# WirelessJoystick.net
KiCad netlist of a schematic drawn in Altium Designer
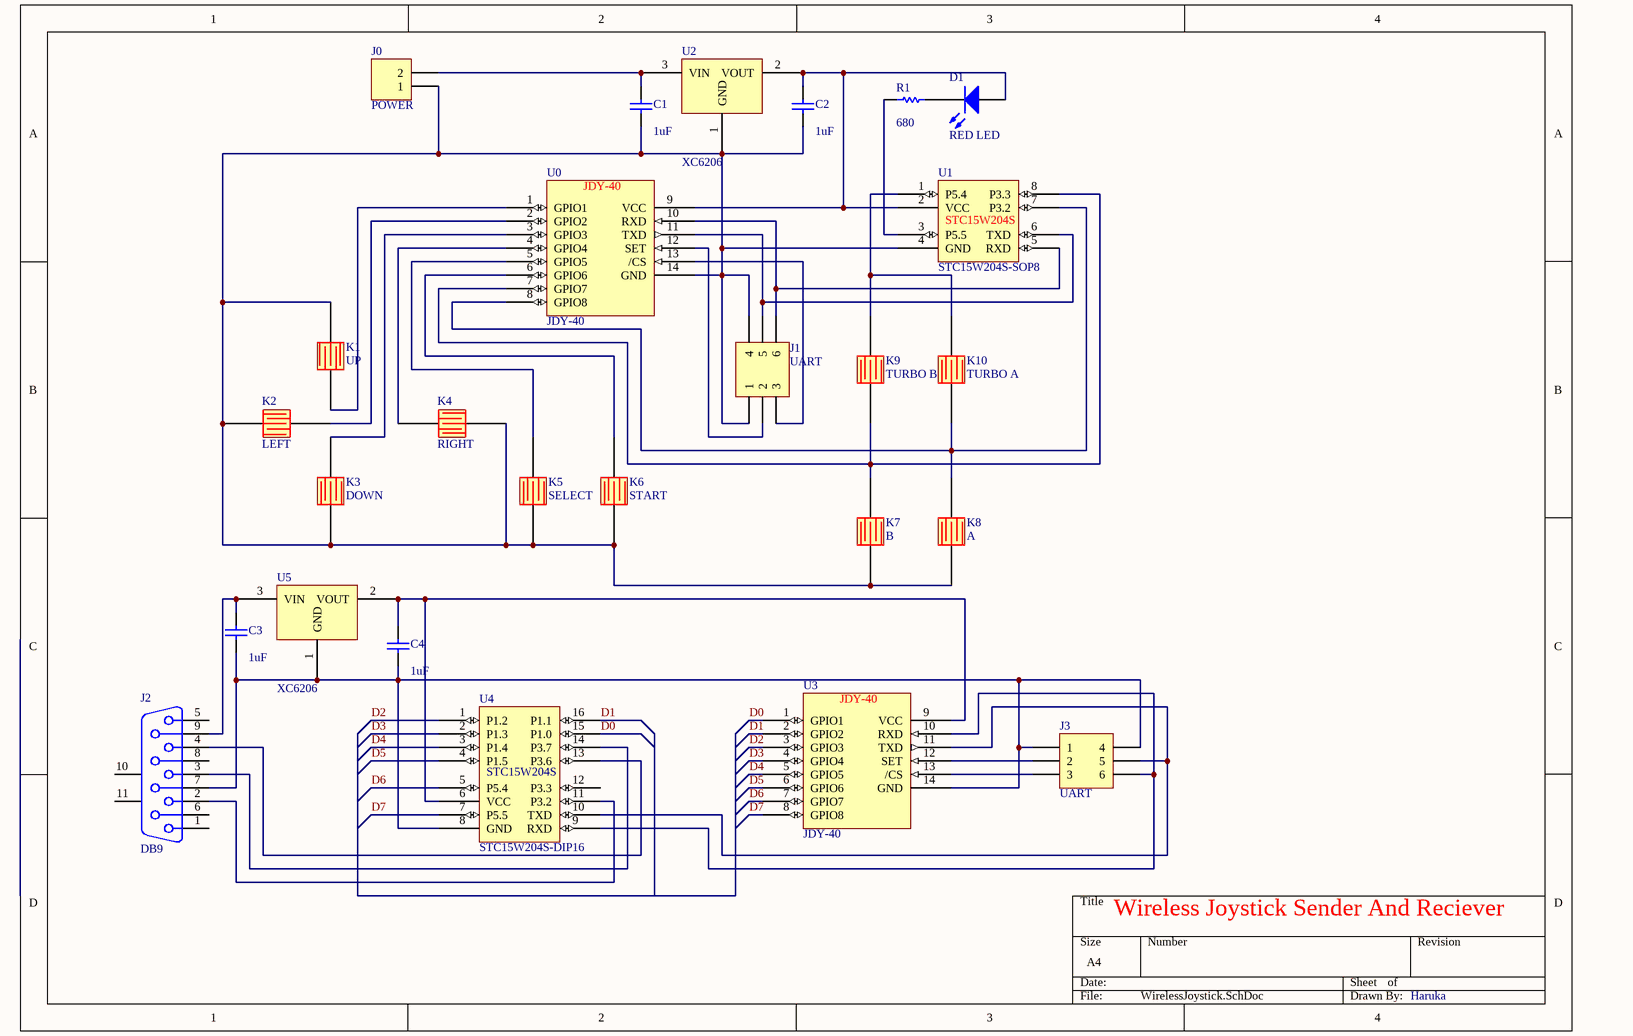
[diagram p0: WirelessJoystick.SchDoc]

(export (version "E")
  (design (tool "Eeschema 10.0.6"))
  (components
    (comp (ref "C1")
      (value "1uF")
      (footprint "C1206")
      (description "Capacitor (Semiconductor SIM Model)")
      (fields (field (name "Comment") "Cap Semi") (field (name "PUBLISHER") "Altium Limited"))
      (libsource (lib "Miscellaneous Devices") (part "Cap Semi"))
    )
    (comp (ref "C2")
      (value "1uF")
      (footprint "C1206")
      (description "Capacitor (Semiconductor SIM Model)")
      (fields (field (name "Comment") "Cap Semi") (field (name "PUBLISHER") "Altium Limited"))
      (libsource (lib "Miscellaneous Devices") (part "Cap Semi"))
    )
    (comp (ref "C3")
      (value "1uF")
      (footprint "C1206")
      (description "Capacitor (Semiconductor SIM Model)")
      (fields (field (name "Comment") "Cap Semi") (field (name "PUBLISHER") "Altium Limited"))
      (libsource (lib "Miscellaneous Devices") (part "Cap Semi"))
    )
    (comp (ref "C4")
      (value "1uF")
      (footprint "C1206")
      (description "Capacitor (Semiconductor SIM Model)")
      (fields (field (name "Comment") "Cap Semi") (field (name "PUBLISHER") "Altium Limited"))
      (libsource (lib "Miscellaneous Devices") (part "Cap Semi"))
    )
    (comp (ref "D1")
      (value "RED LED")
      (footprint "LED-0")
      (description "Typical INFRARED GaAs LED")
      (fields (field (name "PUBLISHER") "Altium Limited"))
      (libsource (lib "Miscellaneous Devices") (part "LED0"))
    )
    (comp (ref "J0")
      (value "POWER")
      (footprint "HDR1X2")
      (description "Header, 2-Pin")
      (fields (field (name "PUBLISHER") "Altium Limited"))
      (libsource (lib "Miscellaneous Connectors") (part "Header 2"))
    )
    (comp (ref "J1")
      (value "UART")
      (footprint "HDR2X3_CEN")
      (description "Header, 3-Pin, Dual row")
      (fields (field (name "PUBLISHER") "Altium Limited"))
      (libsource (lib "") (part "Header 3X2A_1"))
    )
    (comp (ref "J2")
      (value "DB9")
      (footprint "DSUB1.385-2H9")
      (description "Receptacle Assembly, 9 Position, Right Angle")
      (fields (field (name "PUBLISHER") "Altium Limited"))
      (libsource (lib "Miscellaneous Connectors") (part "D Connector 9"))
    )
    (comp (ref "J3")
      (value "UART")
      (footprint "HDR2X3_CEN")
      (description "Header, 3-Pin, Dual row")
      (fields (field (name "PUBLISHER") "Altium Limited"))
      (libsource (lib "Miscellaneous Connectors") (part "Header 3X2A"))
    )
    (comp (ref "K1") (value "UP") (footprint "GoldFinger") (libsource (lib "") (part "GoldFinger_3")))
    (comp (ref "K2") (value "LEFT") (footprint "GoldFinger") (libsource (lib "") (part "GoldFinger_1")))
    (comp (ref "K3")
      (value "DOWN")
      (footprint "GoldFinger")
      (libsource (lib "GoldFinger") (part "GoldFinger"))
    )
    (comp (ref "K4") (value "RIGHT") (footprint "GoldFinger") (libsource (lib "") (part "GoldFinger_2")))
    (comp (ref "K5")
      (value "SELECT")
      (footprint "GoldFinger")
      (libsource (lib "GoldFinger") (part "GoldFinger"))
    )
    (comp (ref "K6")
      (value "START")
      (footprint "GoldFinger")
      (libsource (lib "GoldFinger") (part "GoldFinger"))
    )
    (comp (ref "K7") (value "B") (footprint "GoldFinger") (libsource (lib "GoldFinger") (part "GoldFinger")))
    (comp (ref "K8") (value "A") (footprint "GoldFinger") (libsource (lib "GoldFinger") (part "GoldFinger")))
    (comp (ref "K9")
      (value "TURBO B")
      (footprint "GoldFinger")
      (libsource (lib "GoldFinger") (part "GoldFinger"))
    )
    (comp (ref "K10")
      (value "TURBO A")
      (footprint "GoldFinger")
      (libsource (lib "GoldFinger") (part "GoldFinger"))
    )
    (comp (ref "R1")
      (value "680")
      (footprint "AXIAL-0.3")
      (description "Resistor")
      (fields (field (name "PUBLISHER") "Altium Limited"))
      (libsource (lib "Miscellaneous Devices") (part "Res1"))
    )
    (comp (ref "U0") (value "JDY-40") (footprint "JDY-401") (libsource (lib "JDY-40") (part "JDY-40")))
    (comp (ref "U1")
      (value "STC15W204S-SOP8")
      (footprint "SOP8")
      (libsource (lib "STC15W204S") (part "STC15W204S-SOP8"))
    )
    (comp (ref "U2") (value "XC6206") (footprint "SOT23-3N") (libsource (lib "XC6206") (part "XC6206")))
    (comp (ref "U3") (value "JDY-40") (footprint "JDY-401") (libsource (lib "JDY-40") (part "JDY-40")))
    (comp (ref "U4")
      (value "STC15W204S-DIP16")
      (footprint "DIP16")
      (libsource (lib "STC15W204S") (part "STC15W204S-DIP16"))
    )
    (comp (ref "U5") (value "XC6206") (footprint "SOT23-3N") (libsource (lib "XC6206") (part "XC6206")))
  )
  (nets
    (net (code "1") (name "/D0") (class "Default")
      (node (ref "U3") (pin "1") (pinfunction "GPIO1_1") (pintype "bidirectional"))
      (node (ref "U4") (pin "15") (pinfunction "P1.0_15") (pintype "bidirectional"))
    )
    (net (code "2") (name "/D1") (class "Default")
      (node (ref "U3") (pin "2") (pinfunction "GPIO2_2") (pintype "bidirectional"))
      (node (ref "U4") (pin "16") (pinfunction "P1.1_16") (pintype "bidirectional"))
    )
    (net (code "3") (name "/D2") (class "Default")
      (node (ref "U3") (pin "3") (pinfunction "GPIO3_3") (pintype "bidirectional"))
      (node (ref "U4") (pin "1") (pinfunction "P1.2_1") (pintype "bidirectional"))
    )
    (net (code "4") (name "/D3") (class "Default")
      (node (ref "U3") (pin "4") (pinfunction "GPIO4_4") (pintype "bidirectional"))
      (node (ref "U4") (pin "2") (pinfunction "P1.3_2") (pintype "bidirectional"))
    )
    (net (code "5") (name "/D4") (class "Default")
      (node (ref "U3") (pin "5") (pinfunction "GPIO5_5") (pintype "bidirectional"))
      (node (ref "U4") (pin "3") (pinfunction "P1.4_3") (pintype "bidirectional"))
    )
    (net (code "6") (name "/D5") (class "Default")
      (node (ref "U3") (pin "6") (pinfunction "GPIO6_6") (pintype "bidirectional"))
      (node (ref "U4") (pin "4") (pinfunction "P1.5_4") (pintype "bidirectional"))
    )
    (net (code "7") (name "/D6") (class "Default")
      (node (ref "U3") (pin "7") (pinfunction "GPIO7_7") (pintype "bidirectional"))
      (node (ref "U4") (pin "5") (pinfunction "P5.4_5") (pintype "bidirectional"))
    )
    (net (code "8") (name "/D7") (class "Default")
      (node (ref "U3") (pin "8") (pinfunction "GPIO8_8") (pintype "bidirectional"))
      (node (ref "U4") (pin "7") (pinfunction "P5.5_7") (pintype "bidirectional"))
    )
    (net (code "9") (name "Net-(D1-A)") (class "Default")
      (node (ref "C2") (pin "2") (pinfunction "2_2") (pintype "passive"))
      (node (ref "D1") (pin "1") (pinfunction "A_1") (pintype "passive"))
      (node (ref "U0") (pin "9") (pinfunction "VCC_9") (pintype "power_in"))
      (node (ref "U1") (pin "2") (pinfunction "VCC_2") (pintype "power_in"))
      (node (ref "U2") (pin "2") (pinfunction "VOUT_2") (pintype "power_in"))
    )
    (net (code "10") (name "Net-(D1-K)") (class "Default")
      (node (ref "D1") (pin "2") (pinfunction "K_2") (pintype "passive"))
      (node (ref "R1") (pin "2") (pinfunction "2_2") (pintype "passive"))
    )
    (net (code "11") (name "Net-(K1-PIN_1)") (class "Default")
      (node (ref "C1") (pin "1") (pinfunction "1_1") (pintype "passive"))
      (node (ref "C2") (pin "1") (pinfunction "1_1") (pintype "passive"))
      (node (ref "J0") (pin "1") (pinfunction "1_1") (pintype "passive"))
      (node (ref "J1") (pin "1") (pinfunction "1_1") (pintype "passive"))
      (node (ref "J1") (pin "4") (pinfunction "4_4") (pintype "passive"))
      (node (ref "K1") (pin "1") (pinfunction "PIN_1_1") (pintype "passive"))
      (node (ref "K2") (pin "1") (pinfunction "PIN_1_1") (pintype "passive"))
      (node (ref "K3") (pin "1") (pinfunction "PIN_1_1") (pintype "passive"))
      (node (ref "K4") (pin "1") (pinfunction "PIN_1_1") (pintype "passive"))
      (node (ref "K5") (pin "1") (pinfunction "PIN_1_1") (pintype "passive"))
      (node (ref "K6") (pin "1") (pinfunction "PIN_1_1") (pintype "passive"))
      (node (ref "K7") (pin "1") (pinfunction "PIN_1_1") (pintype "passive"))
      (node (ref "K8") (pin "1") (pinfunction "PIN_1_1") (pintype "passive"))
      (node (ref "U0") (pin "14") (pinfunction "GND_14") (pintype "power_in"))
      (node (ref "U1") (pin "4") (pinfunction "GND_4") (pintype "power_in"))
      (node (ref "U2") (pin "1") (pinfunction "GND_1") (pintype "power_in"))
    )
    (net (code "12") (name "Net-(K1-PIN_2)") (class "Default")
      (node (ref "K1") (pin "2") (pinfunction "PIN_2_2") (pintype "passive"))
      (node (ref "U0") (pin "1") (pinfunction "GPIO1_1") (pintype "bidirectional"))
    )
    (net (code "13") (name "Net-(K2-PIN_2)") (class "Default")
      (node (ref "K2") (pin "2") (pinfunction "PIN_2_2") (pintype "passive"))
      (node (ref "U0") (pin "2") (pinfunction "GPIO2_2") (pintype "bidirectional"))
    )
    (net (code "14") (name "Net-(K3-PIN_2)") (class "Default")
      (node (ref "K3") (pin "2") (pinfunction "PIN_2_2") (pintype "passive"))
      (node (ref "U0") (pin "3") (pinfunction "GPIO3_3") (pintype "bidirectional"))
    )
    (net (code "15") (name "Net-(K4-PIN_2)") (class "Default")
      (node (ref "K4") (pin "2") (pinfunction "PIN_2_2") (pintype "passive"))
      (node (ref "U0") (pin "4") (pinfunction "GPIO4_4") (pintype "bidirectional"))
    )
    (net (code "16") (name "Net-(K5-PIN_2)") (class "Default")
      (node (ref "K5") (pin "2") (pinfunction "PIN_2_2") (pintype "passive"))
      (node (ref "U0") (pin "5") (pinfunction "GPIO5_5") (pintype "bidirectional"))
    )
    (net (code "17") (name "Net-(K6-PIN_2)") (class "Default")
      (node (ref "K6") (pin "2") (pinfunction "PIN_2_2") (pintype "passive"))
      (node (ref "U0") (pin "6") (pinfunction "GPIO6_6") (pintype "bidirectional"))
    )
    (net (code "18") (name "Net-(K7-PIN_2)") (class "Default")
      (node (ref "K7") (pin "2") (pinfunction "PIN_2_2") (pintype "passive"))
      (node (ref "K9") (pin "1") (pinfunction "PIN_1_1") (pintype "passive"))
      (node (ref "U0") (pin "7") (pinfunction "GPIO7_7") (pintype "bidirectional"))
      (node (ref "U1") (pin "8") (pinfunction "P3.3_8") (pintype "bidirectional"))
    )
    (net (code "19") (name "Net-(K10-PIN_1)") (class "Default")
      (node (ref "K10") (pin "1") (pinfunction "PIN_1_1") (pintype "passive"))
      (node (ref "K8") (pin "2") (pinfunction "PIN_2_2") (pintype "passive"))
      (node (ref "U0") (pin "8") (pinfunction "GPIO8_8") (pintype "bidirectional"))
      (node (ref "U1") (pin "7") (pinfunction "P3.2_7") (pintype "bidirectional"))
    )
    (net (code "20") (name "Net-(K10-PIN_2)") (class "Default")
      (node (ref "K10") (pin "2") (pinfunction "PIN_2_2") (pintype "passive"))
      (node (ref "K9") (pin "2") (pinfunction "PIN_2_2") (pintype "passive"))
      (node (ref "U1") (pin "1") (pinfunction "P5.4_1") (pintype "bidirectional"))
    )
    (net (code "21") (name "Net-(U0-RXD)") (class "Default")
      (node (ref "J1") (pin "6") (pinfunction "6_6") (pintype "passive"))
      (node (ref "U0") (pin "10") (pinfunction "RXD_10") (pintype "input"))
      (node (ref "U1") (pin "5") (pinfunction "RXD_5") (pintype "bidirectional"))
    )
    (net (code "22") (name "Net-(U0-SET)") (class "Default")
      (node (ref "J1") (pin "2") (pinfunction "2_2") (pintype "passive"))
      (node (ref "U0") (pin "12") (pinfunction "SET_12") (pintype "input"))
    )
    (net (code "23") (name "Net-(U0-TXD)") (class "Default")
      (node (ref "J1") (pin "5") (pinfunction "5_5") (pintype "passive"))
      (node (ref "U0") (pin "11") (pinfunction "TXD_11") (pintype "output"))
      (node (ref "U1") (pin "6") (pinfunction "TXD_6") (pintype "bidirectional"))
    )
    (net (code "24") (name "Net-(U0-{slash}CS)") (class "Default")
      (node (ref "J1") (pin "3") (pinfunction "3_3") (pintype "passive"))
      (node (ref "U0") (pin "13") (pinfunction "/CS_13") (pintype "input"))
    )
    (net (code "25") (name "Net-(U1-P5.5)") (class "Default")
      (node (ref "R1") (pin "1") (pinfunction "1_1") (pintype "passive"))
      (node (ref "U1") (pin "3") (pinfunction "P5.5_3") (pintype "bidirectional"))
    )
    (net (code "26") (name "Net-(U2-VIN)") (class "Default")
      (node (ref "C1") (pin "2") (pinfunction "2_2") (pintype "passive"))
      (node (ref "J0") (pin "2") (pinfunction "2_2") (pintype "passive"))
      (node (ref "U2") (pin "3") (pinfunction "VIN_3") (pintype "power_in"))
    )
    (net (code "27") (name "Net-(U3-GND)") (class "Default")
      (node (ref "C3") (pin "1") (pinfunction "1_1") (pintype "passive"))
      (node (ref "C4") (pin "1") (pinfunction "1_1") (pintype "passive"))
      (node (ref "J2") (pin "7") (pinfunction "7_7") (pintype "passive"))
      (node (ref "J3") (pin "1") (pinfunction "1_1") (pintype "passive"))
      (node (ref "J3") (pin "4") (pinfunction "4_4") (pintype "passive"))
      (node (ref "U3") (pin "14") (pinfunction "GND_14") (pintype "power_in"))
      (node (ref "U4") (pin "8") (pinfunction "GND_8") (pintype "power_in"))
      (node (ref "U5") (pin "1") (pinfunction "GND_1") (pintype "power_in"))
    )
    (net (code "28") (name "Net-(U3-RXD)") (class "Default")
      (node (ref "J3") (pin "6") (pinfunction "6_6") (pintype "passive"))
      (node (ref "U3") (pin "10") (pinfunction "RXD_10") (pintype "input"))
      (node (ref "U4") (pin "9") (pinfunction "RXD_9") (pintype "bidirectional"))
    )
    (net (code "29") (name "Net-(U3-SET)") (class "Default")
      (node (ref "J3") (pin "2") (pinfunction "2_2") (pintype "passive"))
      (node (ref "U3") (pin "12") (pinfunction "SET_12") (pintype "input"))
    )
    (net (code "30") (name "Net-(U3-TXD)") (class "Default")
      (node (ref "J3") (pin "5") (pinfunction "5_5") (pintype "passive"))
      (node (ref "U3") (pin "11") (pinfunction "TXD_11") (pintype "output"))
      (node (ref "U4") (pin "10") (pinfunction "TXD_10") (pintype "bidirectional"))
    )
    (net (code "31") (name "Net-(U3-VCC)") (class "Default")
      (node (ref "C4") (pin "2") (pinfunction "2_2") (pintype "passive"))
      (node (ref "U3") (pin "9") (pinfunction "VCC_9") (pintype "power_in"))
      (node (ref "U4") (pin "6") (pinfunction "VCC_6") (pintype "power_in"))
      (node (ref "U5") (pin "2") (pinfunction "VOUT_2") (pintype "power_in"))
    )
    (net (code "32") (name "Net-(U3-{slash}CS)") (class "Default")
      (node (ref "J3") (pin "3") (pinfunction "3_3") (pintype "passive"))
      (node (ref "U3") (pin "13") (pinfunction "/CS_13") (pintype "input"))
    )
    (net (code "33") (name "Net-(U4-P3.2)") (class "Default")
      (node (ref "J2") (pin "2") (pinfunction "2_2") (pintype "passive"))
      (node (ref "U4") (pin "11") (pinfunction "P3.2_11") (pintype "bidirectional"))
    )
    (net (code "34") (name "Net-(U4-P3.6)") (class "Default")
      (node (ref "J2") (pin "4") (pinfunction "4_4") (pintype "passive"))
      (node (ref "U4") (pin "13") (pinfunction "P3.6_13") (pintype "bidirectional"))
    )
    (net (code "35") (name "Net-(U4-P3.7)") (class "Default")
      (node (ref "J2") (pin "3") (pinfunction "3_3") (pintype "passive"))
      (node (ref "U4") (pin "14") (pinfunction "P3.7_14") (pintype "bidirectional"))
    )
    (net (code "36") (name "Net-(U5-VIN)") (class "Default")
      (node (ref "C3") (pin "2") (pinfunction "2_2") (pintype "passive"))
      (node (ref "J2") (pin "9") (pinfunction "9_9") (pintype "passive"))
      (node (ref "U5") (pin "3") (pinfunction "VIN_3") (pintype "power_in"))
    )
    (net (code "37") (name "unconnected-(J2-MH1-Pad10)") (class "Default")
      (node (ref "J2") (pin "10") (pinfunction "MH1_10") (pintype "passive"))
    )
    (net (code "38") (name "unconnected-(J2-MH2-Pad11)") (class "Default")
      (node (ref "J2") (pin "11") (pinfunction "MH2_11") (pintype "passive"))
    )
    (net (code "39") (name "unconnected-(J2-Pad1)") (class "Default")
      (node (ref "J2") (pin "1") (pinfunction "1_1") (pintype "passive"))
    )
    (net (code "40") (name "unconnected-(J2-Pad5)") (class "Default")
      (node (ref "J2") (pin "5") (pinfunction "5_5") (pintype "passive"))
    )
    (net (code "41") (name "unconnected-(J2-Pad6)") (class "Default")
      (node (ref "J2") (pin "6") (pinfunction "6_6") (pintype "passive"))
    )
    (net (code "42") (name "unconnected-(J2-Pad8)") (class "Default")
      (node (ref "J2") (pin "8") (pinfunction "8_8") (pintype "passive"))
    )
    (net (code "43") (name "unconnected-(U4-P3.3-Pad12)") (class "Default")
      (node (ref "U4") (pin "12") (pinfunction "P3.3_12") (pintype "bidirectional"))
    )
  )
)
